# board.net
KiCad netlist of a schematic drawn in EAGLE
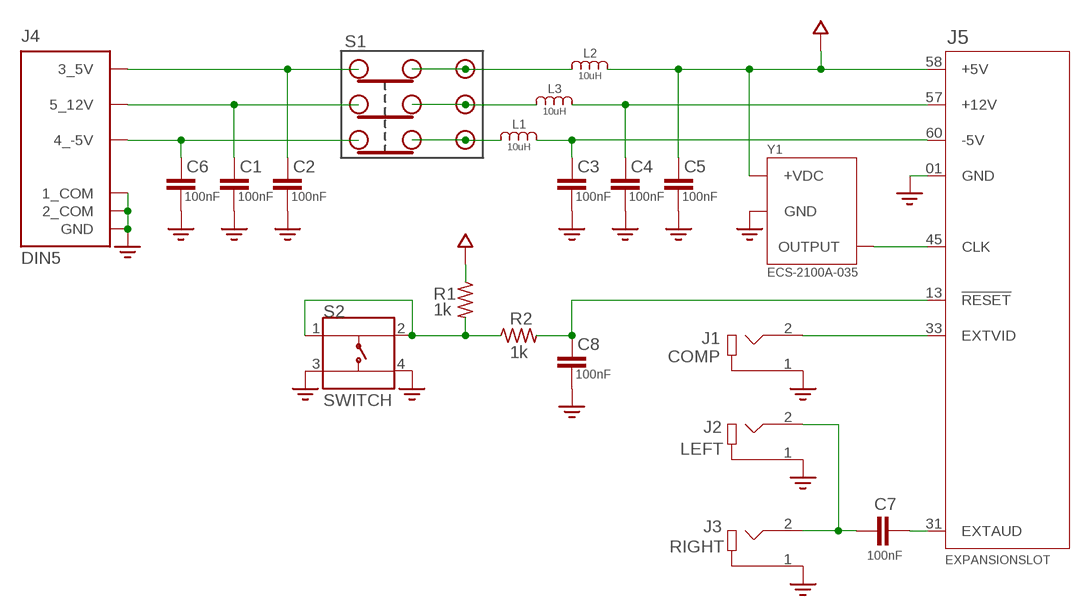
[diagram p0: schematic, sheet 1]

(export (version "E")
  (design (tool "Eeschema 10.0.6"))
  (components
    (comp (ref "C1")
      (value "100nF")
      (footprint "eagle-import:C050-035X075")
      (libsource (lib "eagle-import") (part "CAPACITOR050-035X075"))
    )
    (comp (ref "C2")
      (value "100nF")
      (footprint "eagle-import:C050-035X075")
      (libsource (lib "eagle-import") (part "CAPACITOR050-035X075"))
    )
    (comp (ref "C3")
      (value "100nF")
      (footprint "eagle-import:C050-035X075")
      (libsource (lib "eagle-import") (part "CAPACITOR050-035X075"))
    )
    (comp (ref "C4")
      (value "100nF")
      (footprint "eagle-import:C050-035X075")
      (libsource (lib "eagle-import") (part "CAPACITOR050-035X075"))
    )
    (comp (ref "C5")
      (value "100nF")
      (footprint "eagle-import:C050-035X075")
      (libsource (lib "eagle-import") (part "CAPACITOR050-035X075"))
    )
    (comp (ref "C6")
      (value "100nF")
      (footprint "eagle-import:C050-035X075")
      (libsource (lib "eagle-import") (part "CAPACITOR050-035X075"))
    )
    (comp (ref "C7")
      (value "100nF")
      (footprint "eagle-import:C050-035X075")
      (libsource (lib "eagle-import") (part "CAPACITOR050-035X075"))
    )
    (comp (ref "C8")
      (value "100nF")
      (footprint "eagle-import:C050-035X075")
      (libsource (lib "eagle-import") (part "CAPACITOR050-035X075"))
    )
    (comp (ref "J1")
      (value "COMP")
      (footprint "eagle-import:CUI_RCJ-042")
      (fields (field (name "MF") "CUI Devices") (field (name "MP") "RCJ-042"))
      (libsource (lib "eagle-import") (part "RCA"))
    )
    (comp (ref "J2")
      (value "LEFT")
      (footprint "eagle-import:CUI_RCJ-042")
      (fields (field (name "MF") "CUI Devices") (field (name "MP") "RCJ-042"))
      (libsource (lib "eagle-import") (part "RCA"))
    )
    (comp (ref "J3")
      (value "RIGHT")
      (footprint "eagle-import:CUI_RCJ-042")
      (fields (field (name "MF") "CUI Devices") (field (name "MP") "RCJ-042"))
      (libsource (lib "eagle-import") (part "RCA"))
    )
    (comp (ref "J4")
      (value "DIN5")
      (footprint "eagle-import:CUI_SDS-50J")
      (fields
        (field (name "DIGI-KEY_PART_NUMBER") "CP-2350-ND")
        (field (name "MF") "CUI Devices")
        (field (name "MP") "SDS-50J")
      )
      (libsource (lib "eagle-import") (part "DIN5"))
    )
    (comp (ref "J5")
      (value "EXPANSIONSLOT")
      (footprint "eagle-import:EXPANSIONSLOT")
      (libsource (lib "eagle-import") (part "EXPANSIONSLOT"))
    )
    (comp (ref "L1")
      (value "10uH")
      (footprint "eagle-import:1100R_MUR")
      (fields (field (name "MANUFACTURER_PART_NUMBER") "11R103C"))
      (libsource (lib "eagle-import") (part "INDUCTOR"))
    )
    (comp (ref "L2")
      (value "10uH")
      (footprint "eagle-import:1100R_MUR")
      (fields (field (name "MANUFACTURER_PART_NUMBER") "11R103C"))
      (libsource (lib "eagle-import") (part "INDUCTOR"))
    )
    (comp (ref "L3")
      (value "10uH")
      (footprint "eagle-import:1100R_MUR")
      (fields (field (name "MANUFACTURER_PART_NUMBER") "11R103C"))
      (libsource (lib "eagle-import") (part "INDUCTOR"))
    )
    (comp (ref "R1")
      (value "1k")
      (footprint "eagle-import:0207_10")
      (libsource (lib "eagle-import") (part "RESISTOR0207/10"))
    )
    (comp (ref "R2")
      (value "1k")
      (footprint "eagle-import:0207_10")
      (libsource (lib "eagle-import") (part "RESISTOR0207/10"))
    )
    (comp (ref "S1")
      (value "3PDT")
      (footprint "eagle-import:3PDT")
      (libsource (lib "eagle-import") (part "3PDT"))
    )
    (comp (ref "S2")
      (value "SWITCH")
      (footprint "eagle-import:SW_2-1825910-7")
      (fields
        (field (name "COMMENT") "2-1825910-7")
        (field (name "DIGI-KEY_PART_NUMBER") "450-1642-ND")
        (field (name "MF") "TE Connectivity")
      )
      (libsource (lib "eagle-import") (part "SWITCH"))
    )
    (comp (ref "Y1")
      (value "ECS-2100A-035")
      (footprint "eagle-import:OSC_ECS-2100A-035")
      (fields (field (name "DIGI-KEY_PART_NUMBER") "XC235-ND") (field (name "MF") "ECS Inc."))
      (libsource (lib "eagle-import") (part "ECS-2100A-035"))
    )
  )
  (nets
    (net (code "1") (name "5V") (class "Default")
      (node (ref "C5") (pin "1") (pinfunction "1_1") (pintype "passive"))
      (node (ref "J5") (pin "58") (pinfunction "+5V_58") (pintype "passive"))
      (node (ref "L2") (pin "1") (pinfunction "1_1") (pintype "passive"))
      (node (ref "R1") (pin "1") (pinfunction "1_1") (pintype "passive"))
      (node (ref "Y1") (pin "8") (pinfunction "+VDC_8") (pintype "input"))
    )
    (net (code "2") (name "GND") (class "Default")
      (node (ref "C1") (pin "2") (pinfunction "2_2") (pintype "passive"))
      (node (ref "C2") (pin "2") (pinfunction "2_2") (pintype "passive"))
      (node (ref "C3") (pin "2") (pinfunction "2_2") (pintype "passive"))
      (node (ref "C4") (pin "2") (pinfunction "2_2") (pintype "passive"))
      (node (ref "C5") (pin "2") (pinfunction "2_2") (pintype "passive"))
      (node (ref "C6") (pin "2") (pinfunction "2_2") (pintype "passive"))
      (node (ref "C8") (pin "2") (pinfunction "2_2") (pintype "passive"))
      (node (ref "J1") (pin "1") (pinfunction "1_1") (pintype "passive"))
      (node (ref "J2") (pin "1") (pinfunction "1_1") (pintype "passive"))
      (node (ref "J3") (pin "1") (pinfunction "1_1") (pintype "passive"))
      (node (ref "J4") (pin "1") (pinfunction "1_COM_1") (pintype "passive"))
      (node (ref "J4") (pin "2") (pinfunction "2_COM_2") (pintype "passive"))
      (node (ref "J4") (pin "E1") (pinfunction "GND_E1") (pintype "power_in"))
      (node (ref "J4") (pin "E2") (pinfunction "GND_E2") (pintype "power_in"))
      (node (ref "J5") (pin "01") (pinfunction "GND_01") (pintype "passive"))
      (node (ref "S2") (pin "3") (pinfunction "3_3") (pintype "passive"))
      (node (ref "S2") (pin "4") (pinfunction "4_4") (pintype "passive"))
      (node (ref "Y1") (pin "4") (pinfunction "GND_4") (pintype "power_in"))
    )
    (net (code "3") (name "Net-(C7-Pad2)") (class "Default")
      (node (ref "C7") (pin "2") (pinfunction "2_2") (pintype "passive"))
      (node (ref "J2") (pin "2") (pinfunction "2_2") (pintype "passive"))
      (node (ref "J3") (pin "2") (pinfunction "2_2") (pintype "passive"))
    )
    (net (code "4") (name "Net-(J4-3_5V)") (class "Default")
      (node (ref "C2") (pin "1") (pinfunction "1_1") (pintype "passive"))
      (node (ref "J4") (pin "3") (pinfunction "3_5V_3") (pintype "passive"))
      (node (ref "S1") (pin "P$1C") (pinfunction "P$1C_P$1C") (pintype "bidirectional"))
    )
    (net (code "5") (name "Net-(J4-4_-5V)") (class "Default")
      (node (ref "C6") (pin "1") (pinfunction "1_1") (pintype "passive"))
      (node (ref "J4") (pin "4") (pinfunction "4_-5V_4") (pintype "passive"))
      (node (ref "S1") (pin "P$3C") (pinfunction "P$3C_P$3C") (pintype "bidirectional"))
    )
    (net (code "6") (name "Net-(J4-5_12V)") (class "Default")
      (node (ref "C1") (pin "1") (pinfunction "1_1") (pintype "passive"))
      (node (ref "J4") (pin "5") (pinfunction "5_12V_5") (pintype "passive"))
      (node (ref "S1") (pin "P$2C") (pinfunction "P$2C_P$2C") (pintype "bidirectional"))
    )
    (net (code "7") (name "Net-(J5-+12V)") (class "Default")
      (node (ref "C4") (pin "1") (pinfunction "1_1") (pintype "passive"))
      (node (ref "J5") (pin "57") (pinfunction "+12V_57") (pintype "passive"))
      (node (ref "L3") (pin "1") (pinfunction "1_1") (pintype "passive"))
    )
    (net (code "8") (name "Net-(J5--5V)") (class "Default")
      (node (ref "C3") (pin "1") (pinfunction "1_1") (pintype "passive"))
      (node (ref "J5") (pin "60") (pinfunction "-5V_60") (pintype "passive"))
      (node (ref "L1") (pin "1") (pinfunction "1_1") (pintype "passive"))
    )
    (net (code "9") (name "Net-(J5-CLK)") (class "Default")
      (node (ref "J5") (pin "45") (pinfunction "CLK_45") (pintype "passive"))
      (node (ref "Y1") (pin "5") (pinfunction "OUTPUT_5") (pintype "output"))
    )
    (net (code "10") (name "Net-(J5-EXTAUD)") (class "Default")
      (node (ref "C7") (pin "1") (pinfunction "1_1") (pintype "passive"))
      (node (ref "J5") (pin "31") (pinfunction "EXTAUD_31") (pintype "passive"))
    )
    (net (code "11") (name "Net-(J5-EXTVID)") (class "Default")
      (node (ref "J1") (pin "2") (pinfunction "2_2") (pintype "passive"))
      (node (ref "J5") (pin "33") (pinfunction "EXTVID_33") (pintype "passive"))
    )
    (net (code "12") (name "Net-(J5-~{RESET})") (class "Default")
      (node (ref "C8") (pin "1") (pinfunction "1_1") (pintype "passive"))
      (node (ref "J5") (pin "13") (pinfunction "~{RESET}_13") (pintype "passive"))
      (node (ref "R2") (pin "2") (pinfunction "2_2") (pintype "passive"))
    )
    (net (code "13") (name "Net-(L1-Pad2)") (class "Default")
      (node (ref "L1") (pin "2") (pinfunction "2_2") (pintype "passive"))
      (node (ref "S1") (pin "P$3A") (pinfunction "P$3A_P$3A") (pintype "bidirectional"))
      (node (ref "S1") (pin "P$3B") (pinfunction "P$3B_P$3B") (pintype "bidirectional"))
    )
    (net (code "14") (name "Net-(L2-Pad2)") (class "Default")
      (node (ref "L2") (pin "2") (pinfunction "2_2") (pintype "passive"))
      (node (ref "S1") (pin "P$1A") (pinfunction "P$1A_P$1A") (pintype "bidirectional"))
      (node (ref "S1") (pin "P$1B") (pinfunction "P$1B_P$1B") (pintype "bidirectional"))
    )
    (net (code "15") (name "Net-(L3-Pad2)") (class "Default")
      (node (ref "L3") (pin "2") (pinfunction "2_2") (pintype "passive"))
      (node (ref "S1") (pin "P$2A") (pinfunction "P$2A_P$2A") (pintype "bidirectional"))
      (node (ref "S1") (pin "P$2B") (pinfunction "P$2B_P$2B") (pintype "bidirectional"))
    )
    (net (code "16") (name "Net-(R1-Pad2)") (class "Default")
      (node (ref "R1") (pin "2") (pinfunction "2_2") (pintype "passive"))
      (node (ref "R2") (pin "1") (pinfunction "1_1") (pintype "passive"))
      (node (ref "S2") (pin "1") (pinfunction "1_1") (pintype "passive"))
      (node (ref "S2") (pin "2") (pinfunction "2_2") (pintype "passive"))
    )
  )
)
